# sensor-shield-v5.net
KiCad netlist of a schematic drawn in EasyEDA
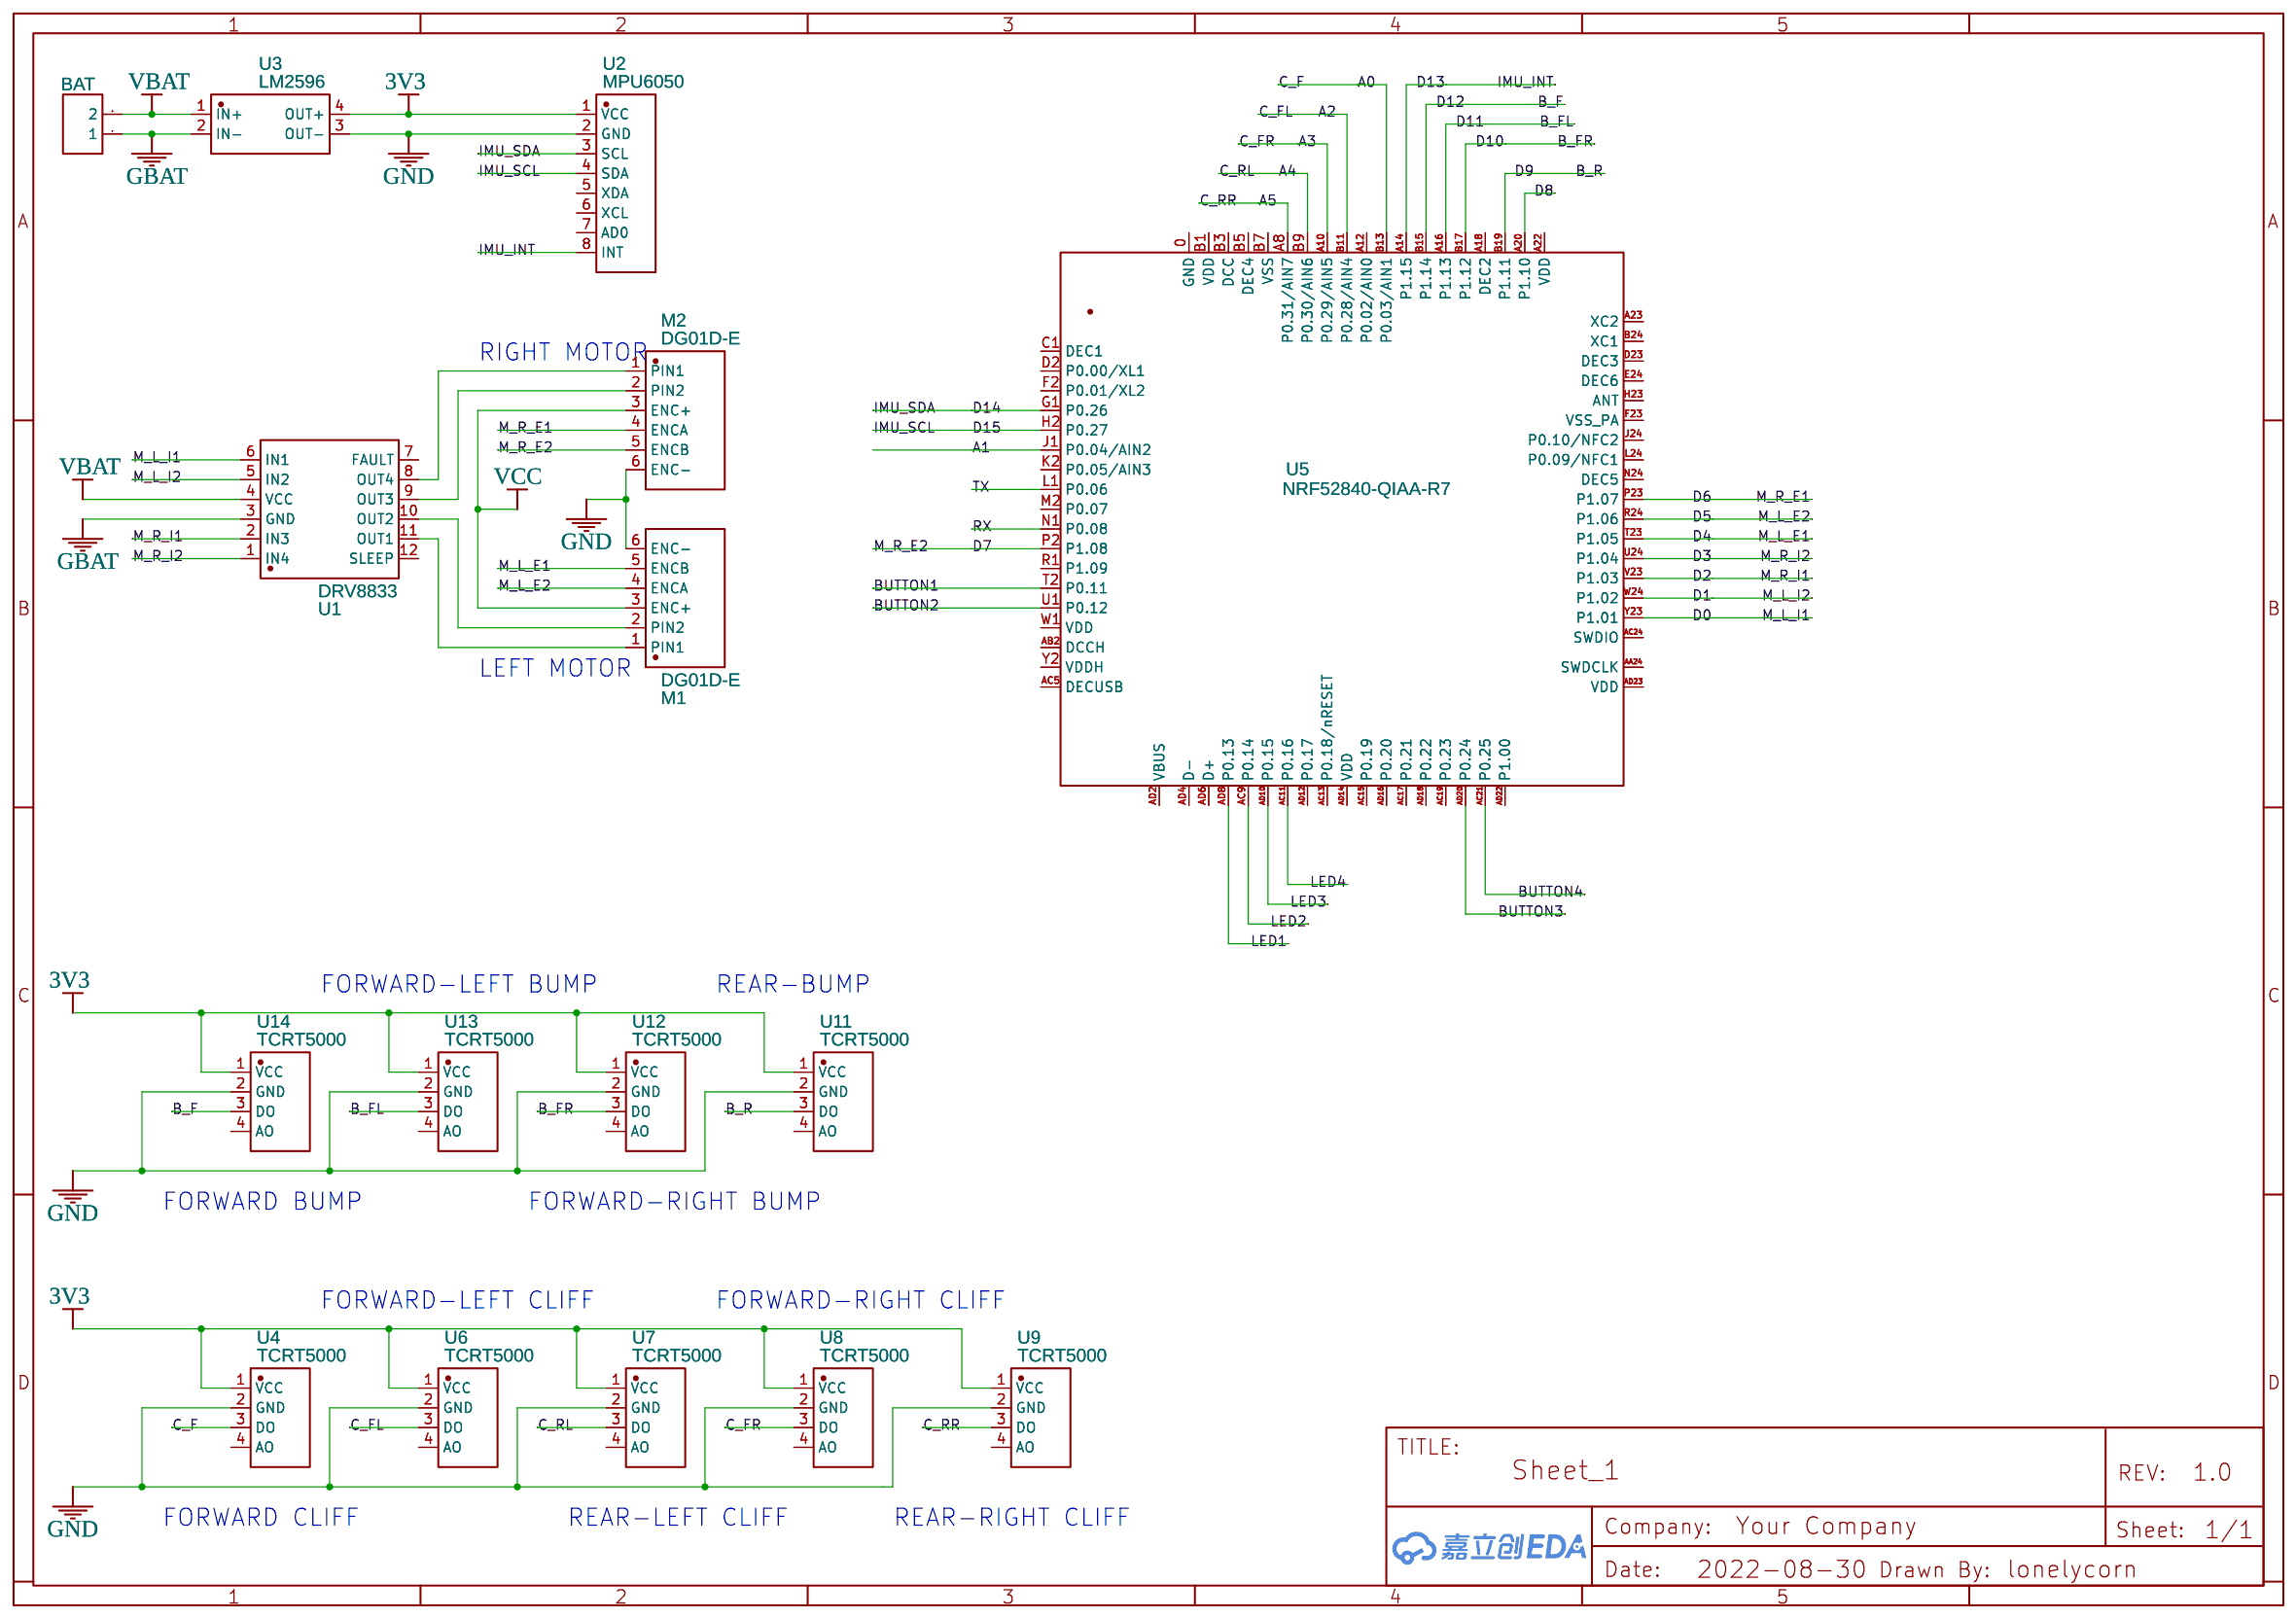
[diagram p0: Sensors]
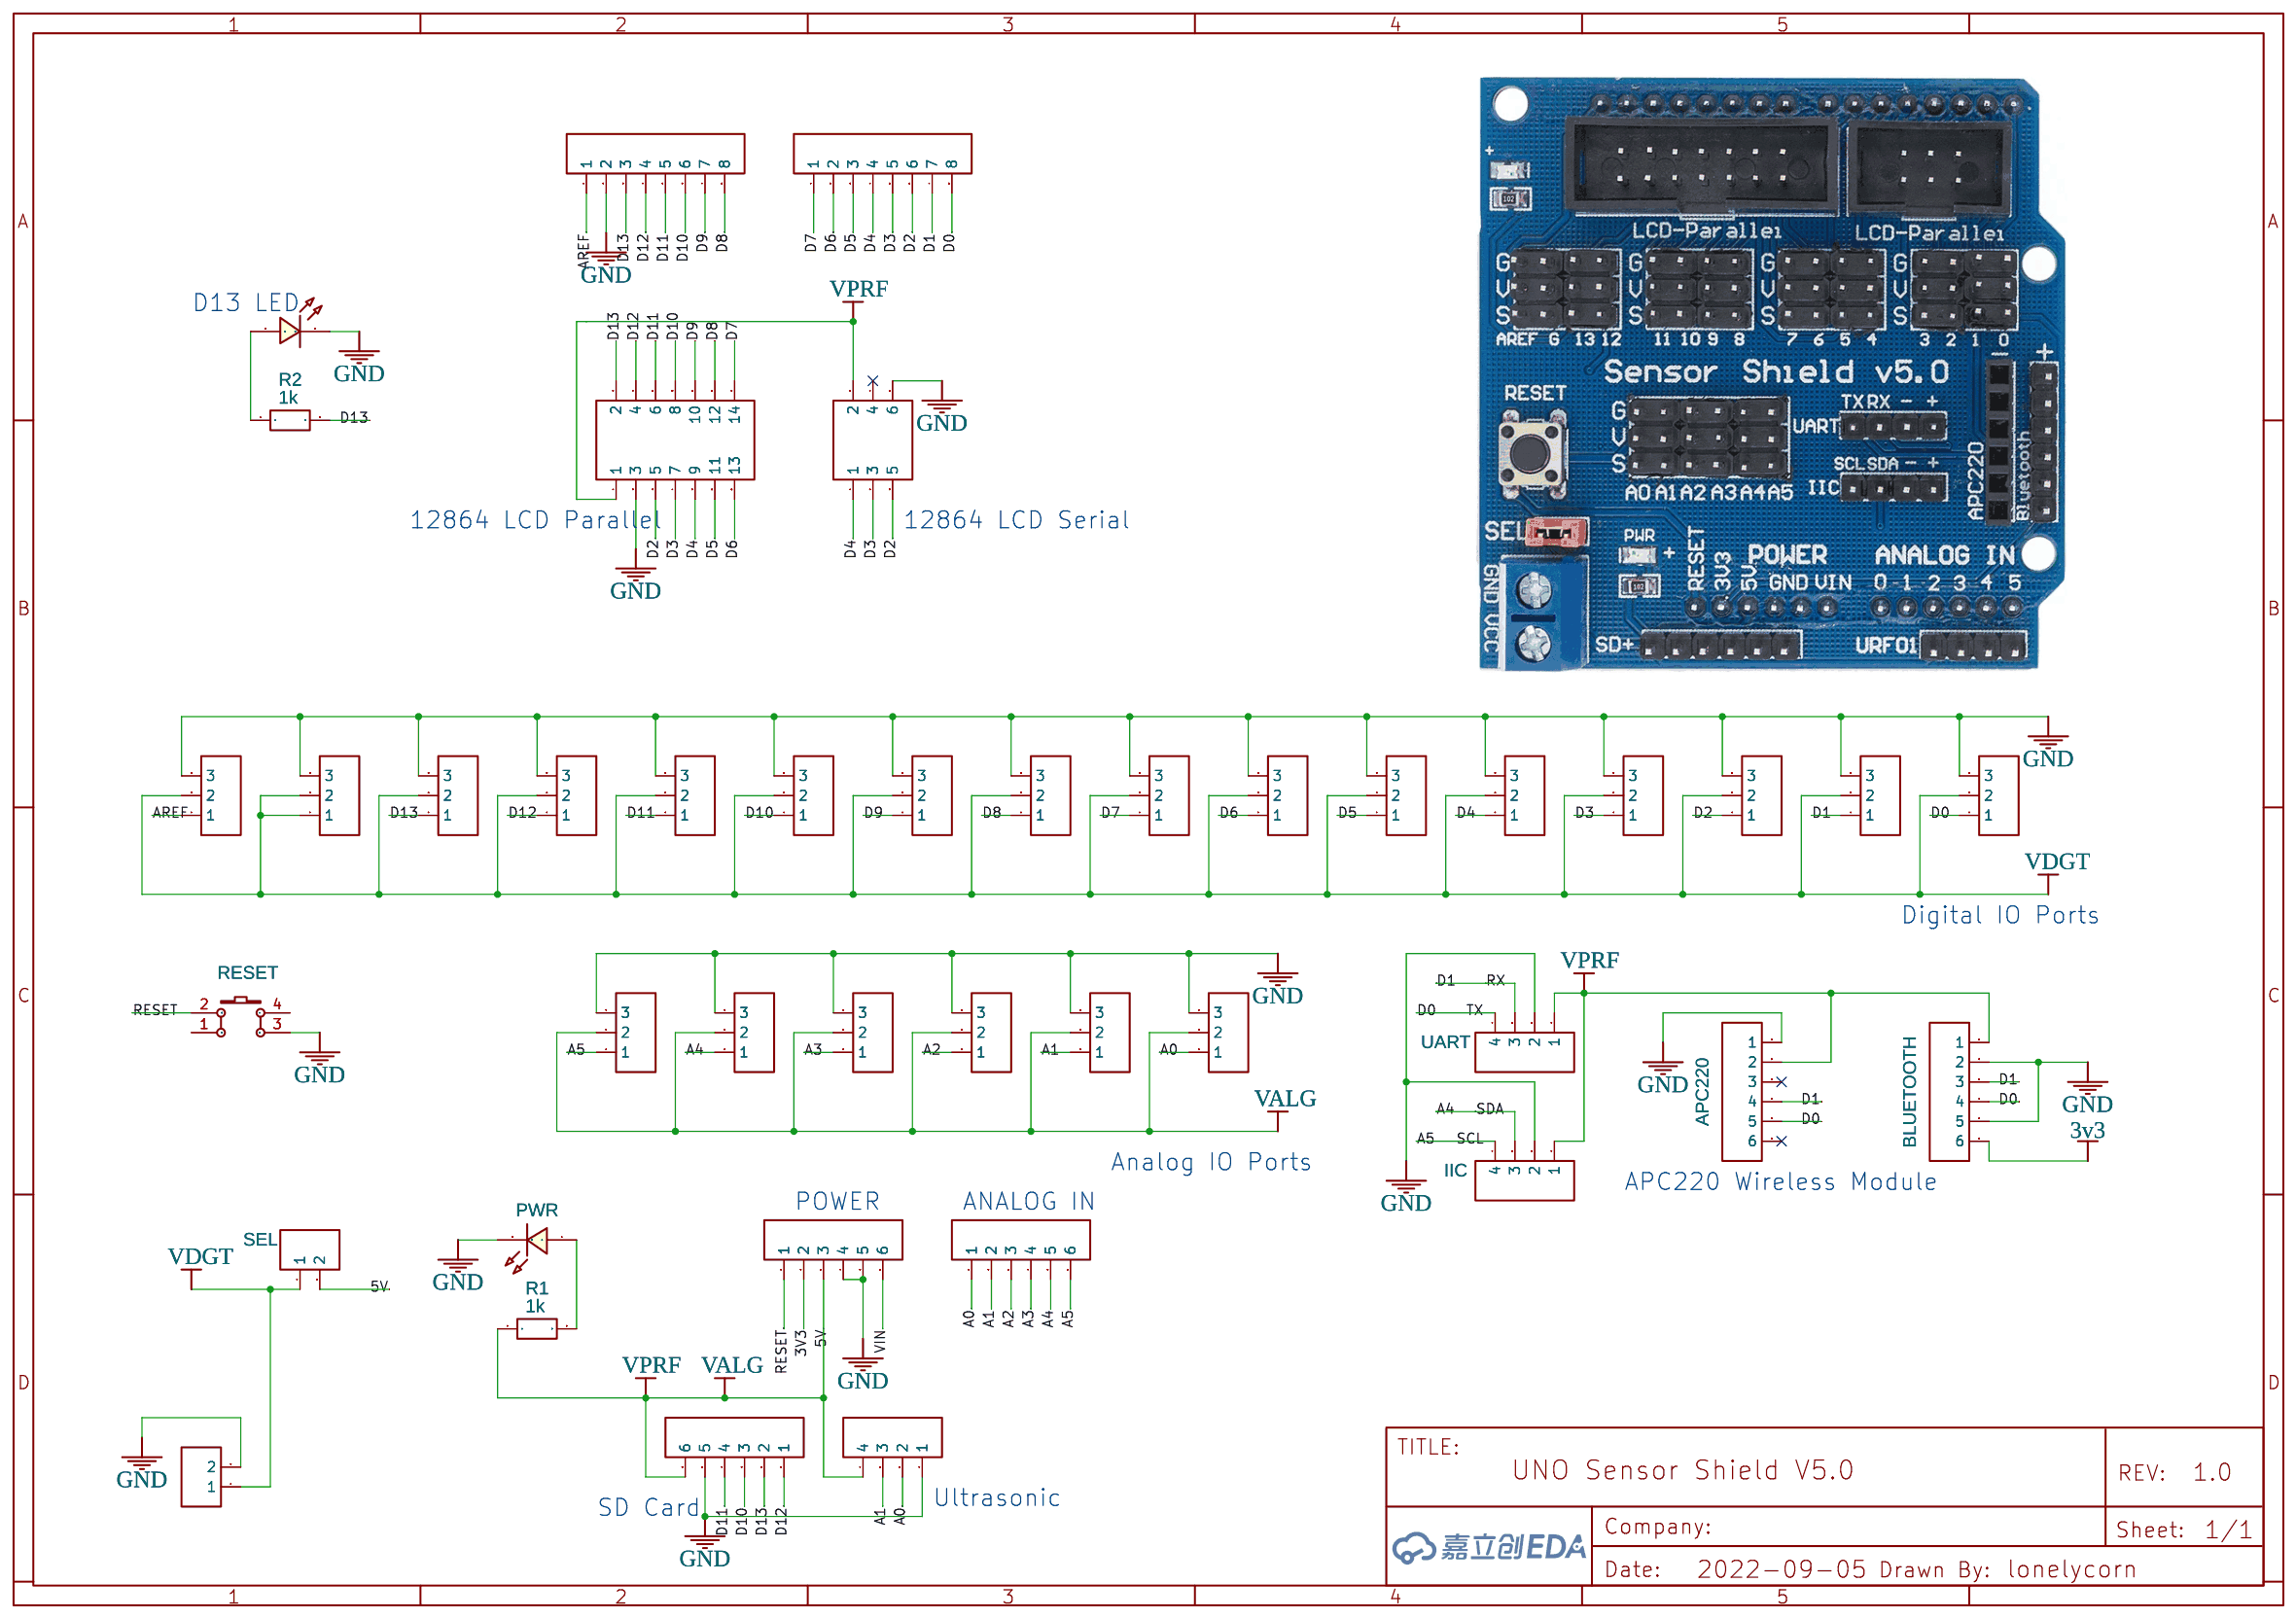
[diagram p1: Sensor Shield v5.0]

(export (version "E")
  (design (tool "Eeschema 10.0.6"))
  (components
    (comp (ref "BAT")
      (value "HDR-F-2.54_1x2")
      (fields (field (name "BOM_Supplier Part") "C49661"))
      (libsource (lib "") (part "HDR-F-2.54_1x2"))
    )
    (comp (ref "M1") (value "DG01D-E") (libsource (lib "") (part "DG01D-E")))
    (comp (ref "M2") (value "DG01D-E") (libsource (lib "") (part "DG01D-E_1")))
    (comp (ref "U1") (value "DRV8833") (libsource (lib "") (part "DRV8833")))
    (comp (ref "U2") (value "MPU6050") (libsource (lib "") (part "MPU6050")))
    (comp (ref "U3") (value "LM2596") (libsource (lib "") (part "LM2596")))
    (comp (ref "U4") (value "TCRT5000") (libsource (lib "") (part "TCRT5000")))
    (comp (ref "U5")
      (value "NRF52840-QIAA-R7")
      (fields (field (name "BOM_Supplier Part") "C1851953"))
      (libsource (lib "") (part "NRF52840-QIAA-R7"))
    )
    (comp (ref "U6") (value "TCRT5000") (libsource (lib "") (part "TCRT5000")))
    (comp (ref "U7") (value "TCRT5000") (libsource (lib "") (part "TCRT5000")))
    (comp (ref "U8") (value "TCRT5000") (libsource (lib "") (part "TCRT5000")))
    (comp (ref "U9") (value "TCRT5000") (libsource (lib "") (part "TCRT5000")))
    (comp (ref "U11") (value "TCRT5000") (libsource (lib "") (part "TCRT5000")))
    (comp (ref "U12") (value "TCRT5000") (libsource (lib "") (part "TCRT5000")))
    (comp (ref "U13") (value "TCRT5000") (libsource (lib "") (part "TCRT5000")))
    (comp (ref "U14") (value "TCRT5000") (libsource (lib "") (part "TCRT5000")))
    (comp (ref "APC220")
      (value "HDR-F-2.54_1x6")
      (fields (field (name "BOM_Supplier Part") "C40877"))
      (libsource (lib "") (part "HDR-F-2.54_1x6_1"))
    )
    (comp (ref "BLUETOOTH")
      (value "HDR-M-2.54_1x6")
      (fields (field (name "BOM_Supplier Part") "C40877"))
      (libsource (lib "") (part "HDR-F-2.54_1x6"))
    )
    (comp (ref "D0")
      (value "HDR-M-2.54_1x3")
      (fields (field (name "BOM_Supplier Part") "C146690"))
      (libsource (lib "") (part "HDR-F-2.54_1x3"))
    )
    (comp (ref "D1")
      (value "HDR-M-2.54_1x3")
      (fields (field (name "BOM_Supplier Part") "C146690"))
      (libsource (lib "") (part "HDR-F-2.54_1x3"))
    )
    (comp (ref "D2")
      (value "HDR-M-2.54_1x3")
      (fields (field (name "BOM_Supplier Part") "C146690"))
      (libsource (lib "") (part "HDR-F-2.54_1x3"))
    )
    (comp (ref "D3")
      (value "HDR-M-2.54_1x3")
      (fields (field (name "BOM_Supplier Part") "C146690"))
      (libsource (lib "") (part "HDR-F-2.54_1x3"))
    )
    (comp (ref "D4")
      (value "HDR-M-2.54_1x3")
      (fields (field (name "BOM_Supplier Part") "C146690"))
      (libsource (lib "") (part "HDR-F-2.54_1x3"))
    )
    (comp (ref "D5")
      (value "HDR-M-2.54_1x3")
      (fields (field (name "BOM_Supplier Part") "C146690"))
      (libsource (lib "") (part "HDR-F-2.54_1x3"))
    )
    (comp (ref "D6")
      (value "HDR-M-2.54_1x3")
      (fields (field (name "BOM_Supplier Part") "C146690"))
      (libsource (lib "") (part "HDR-F-2.54_1x3"))
    )
    (comp (ref "D7")
      (value "HDR-M-2.54_1x3")
      (fields (field (name "BOM_Supplier Part") "C146690"))
      (libsource (lib "") (part "HDR-F-2.54_1x3"))
    )
    (comp (ref "D8")
      (value "HDR-M-2.54_1x3")
      (fields (field (name "BOM_Supplier Part") "C146690"))
      (libsource (lib "") (part "HDR-F-2.54_1x3"))
    )
    (comp (ref "D9")
      (value "HDR-M-2.54_1x3")
      (fields (field (name "BOM_Supplier Part") "C146690"))
      (libsource (lib "") (part "HDR-F-2.54_1x3"))
    )
    (comp (ref "D10")
      (value "HDR-M-2.54_1x3")
      (fields (field (name "BOM_Supplier Part") "C146690"))
      (libsource (lib "") (part "HDR-F-2.54_1x3"))
    )
    (comp (ref "D11")
      (value "HDR-M-2.54_1x3")
      (fields (field (name "BOM_Supplier Part") "C146690"))
      (libsource (lib "") (part "HDR-F-2.54_1x3"))
    )
    (comp (ref "D12")
      (value "HDR-M-2.54_1x3")
      (fields (field (name "BOM_Supplier Part") "C146690"))
      (libsource (lib "") (part "HDR-F-2.54_1x3"))
    )
    (comp (ref "D13")
      (value "HDR-M-2.54_1x3")
      (fields (field (name "BOM_Supplier Part") "C146690"))
      (libsource (lib "") (part "HDR-F-2.54_1x3"))
    )
    (comp (ref "D14")
      (value "HDR-M-2.54_1x3")
      (fields (field (name "BOM_Supplier Part") "C146690"))
      (libsource (lib "") (part "HDR-F-2.54_1x3"))
    )
    (comp (ref "D15")
      (value "HDR-M-2.54_1x3")
      (fields (field (name "BOM_Supplier Part") "C146690"))
      (libsource (lib "") (part "HDR-F-2.54_1x3"))
    )
    (comp (ref "D16")
      (value "HDR-M-2.54_1x3")
      (fields (field (name "BOM_Supplier Part") "C146690"))
      (libsource (lib "") (part "HDR-F-2.54_1x3"))
    )
    (comp (ref "D17")
      (value "HDR-M-2.54_1x3")
      (fields (field (name "BOM_Supplier Part") "C146690"))
      (libsource (lib "") (part "HDR-F-2.54_1x3"))
    )
    (comp (ref "D18")
      (value "HDR-M-2.54_1x3")
      (fields (field (name "BOM_Supplier Part") "C146690"))
      (libsource (lib "") (part "HDR-F-2.54_1x3"))
    )
    (comp (ref "D19")
      (value "HDR-M-2.54_1x3")
      (fields (field (name "BOM_Supplier Part") "C146690"))
      (libsource (lib "") (part "HDR-F-2.54_1x3"))
    )
    (comp (ref "H1")
      (value "HDR-M-2.54_1x3")
      (fields (field (name "BOM_Supplier Part") "C146690"))
      (libsource (lib "") (part "HDR-F-2.54_1x3_1"))
    )
    (comp (ref "H2")
      (value "HDR-M-2.54_1x3")
      (fields (field (name "BOM_Supplier Part") "C146690"))
      (libsource (lib "") (part "HDR-F-2.54_1x3_1"))
    )
    (comp (ref "H4")
      (value "HDR-F-2.54_2x3")
      (fields (field (name "BOM_Supplier Part") "C65114"))
      (libsource (lib "") (part "HDR-F-2.54_2x3"))
    )
    (comp (ref "IIC")
      (value "HDR-M-2.54_1x4")
      (fields (field (name "BOM_Supplier Part") "C225501"))
      (libsource (lib "") (part "HDR-F-2.54_1x4_1"))
    )
    (comp (ref "J1")
      (value "HDR-M-2.54_1x8")
      (fields (field (name "BOM_Supplier Part") "C190820"))
      (libsource (lib "") (part "HDR-M-2.54_1x8"))
    )
    (comp (ref "J2")
      (value "HDR-M-2.54_1x8")
      (fields (field (name "BOM_Supplier Part") "C190820"))
      (libsource (lib "") (part "HDR-M-2.54_1x8"))
    )
    (comp (ref "J3")
      (value "HDR-M-2.54_1x6")
      (fields (field (name "BOM_Supplier Part") "C190819"))
      (libsource (lib "") (part "HDR-M-2.54_1x6"))
    )
    (comp (ref "J4")
      (value "HDR-M-2.54_1x6")
      (fields (field (name "BOM_Supplier Part") "C190819"))
      (libsource (lib "") (part "HDR-M-2.54_1x6"))
    )
    (comp (ref "J5")
      (value "HDR-M-2.54_1x6")
      (fields (field (name "BOM_Supplier Part") "C190819"))
      (libsource (lib "") (part "HDR-M-2.54_1x6_1"))
    )
    (comp (ref "J6")
      (value "HDR-M-2.54_1x4")
      (fields (field (name "BOM_Supplier Part") "C124378"))
      (libsource (lib "") (part "HDR-M-2.54_1x4"))
    )
    (comp (ref "LCD")
      (value "HDR-F-2.54_2x7")
      (fields (field (name "BOM_Supplier Part") "C38844"))
      (libsource (lib "") (part "HDR-F-2.54_2x7"))
    )
    (comp (ref "LED1")
      (value "LED-0603_R")
      (fields
        (field (name "BOM_Manufacturer Part") "19-217/R6C-AL1M2VY/3T")
        (field (name "BOM_Supplier Part") "C72044")
      )
      (libsource (lib "") (part "LED-0603_R_1"))
    )
    (comp (ref "P1") (value "CONN-TH_2P-P5.00") (libsource (lib "") (part "CONN-TH_2P-P5.00")))
    (comp (ref "PWR")
      (value "LED-0603_R")
      (fields
        (field (name "BOM_Manufacturer Part") "19-217/R6C-AL1M2VY/3T")
        (field (name "BOM_Supplier Part") "C72044")
      )
      (libsource (lib "") (part "LED-0603_R"))
    )
    (comp (ref "R1") (value "1k") (libsource (lib "") (part "R_0402_EU")))
    (comp (ref "R2") (value "1k") (libsource (lib "") (part "R_0402_EU")))
    (comp (ref "RESET")
      (value "K4-6×6_SMD")
      (fields
        (field (name "BOM_Manufacturer Part") "K2-6639SP-D4SC-04")
        (field (name "BOM_Supplier Part") "C191626")
      )
      (libsource (lib "") (part "K4-6×6_SMD"))
    )
    (comp (ref "SEL")
      (value "HDR-M-2.54_1x2")
      (fields (field (name "BOM_Supplier Part") "C124375"))
      (libsource (lib "") (part "HDR-M-2.54_1x2"))
    )
    (comp (ref "UART")
      (value "HDR-M-2.54_1x4")
      (fields (field (name "BOM_Supplier Part") "C225501"))
      (libsource (lib "") (part "HDR-F-2.54_1x4"))
    )
  )
  (nets
    (net (code "1") (name "3V3") (class "Default")
      (node (ref "J3") (pin "2") (pinfunction "2_2") (pintype "input"))
      (node (ref "U11") (pin "1") (pinfunction "VCC_1") (pintype "unspecified"))
      (node (ref "U12") (pin "1") (pinfunction "VCC_1") (pintype "unspecified"))
      (node (ref "U13") (pin "1") (pinfunction "VCC_1") (pintype "unspecified"))
      (node (ref "U14") (pin "1") (pinfunction "VCC_1") (pintype "unspecified"))
      (node (ref "U2") (pin "1") (pinfunction "VCC_1") (pintype "unspecified"))
      (node (ref "U3") (pin "4") (pinfunction "OUT+_4") (pintype "unspecified"))
      (node (ref "U4") (pin "1") (pinfunction "VCC_1") (pintype "unspecified"))
      (node (ref "U6") (pin "1") (pinfunction "VCC_1") (pintype "unspecified"))
      (node (ref "U7") (pin "1") (pinfunction "VCC_1") (pintype "unspecified"))
      (node (ref "U8") (pin "1") (pinfunction "VCC_1") (pintype "unspecified"))
      (node (ref "U9") (pin "1") (pinfunction "VCC_1") (pintype "unspecified"))
    )
    (net (code "2") (name "3v3") (class "Default")
      (node (ref "BLUETOOTH") (pin "6") (pinfunction "6_6") (pintype "input"))
    )
    (net (code "3") (name "5V") (class "Default")
      (node (ref "APC220") (pin "2") (pinfunction "2_2") (pintype "input"))
      (node (ref "BLUETOOTH") (pin "1") (pinfunction "1_1") (pintype "input"))
      (node (ref "D14") (pin "2") (pinfunction "2_2") (pintype "input"))
      (node (ref "D15") (pin "2") (pinfunction "2_2") (pintype "input"))
      (node (ref "D16") (pin "2") (pinfunction "2_2") (pintype "input"))
      (node (ref "D17") (pin "2") (pinfunction "2_2") (pintype "input"))
      (node (ref "D18") (pin "2") (pinfunction "2_2") (pintype "input"))
      (node (ref "D19") (pin "2") (pinfunction "2_2") (pintype "input"))
      (node (ref "H4") (pin "2") (pinfunction "2_2") (pintype "input"))
      (node (ref "IIC") (pin "1") (pinfunction "1_1") (pintype "unspecified"))
      (node (ref "J3") (pin "3") (pinfunction "3_3") (pintype "input"))
      (node (ref "J5") (pin "6") (pinfunction "6_6") (pintype "input"))
      (node (ref "J6") (pin "4") (pinfunction "4_4") (pintype "unspecified"))
      (node (ref "LCD") (pin "1") (pinfunction "1_1") (pintype "input"))
      (node (ref "R1") (pin "1") (pinfunction "1_1") (pintype "unspecified"))
      (node (ref "SEL") (pin "2") (pinfunction "2_2") (pintype "unspecified"))
      (node (ref "UART") (pin "1") (pinfunction "1_1") (pintype "unspecified"))
    )
    (net (code "4") (name "A0") (class "Default")
      (node (ref "D19") (pin "1") (pinfunction "1_1") (pintype "input"))
      (node (ref "J4") (pin "1") (pinfunction "1_1") (pintype "input"))
      (node (ref "J6") (pin "2") (pinfunction "2_2") (pintype "unspecified"))
      (node (ref "U4") (pin "3") (pinfunction "DO_3") (pintype "unspecified"))
      (node (ref "U5") (pin "B13") (pinfunction "P0.03/AIN1_B13") (pintype "unspecified"))
    )
    (net (code "5") (name "A1") (class "Default")
      (node (ref "D18") (pin "1") (pinfunction "1_1") (pintype "input"))
      (node (ref "J4") (pin "2") (pinfunction "2_2") (pintype "input"))
      (node (ref "J6") (pin "3") (pinfunction "3_3") (pintype "unspecified"))
      (node (ref "U5") (pin "J1") (pinfunction "P0.04/AIN2_J1") (pintype "unspecified"))
    )
    (net (code "6") (name "A2") (class "Default")
      (node (ref "D17") (pin "1") (pinfunction "1_1") (pintype "input"))
      (node (ref "J4") (pin "3") (pinfunction "3_3") (pintype "input"))
      (node (ref "U5") (pin "B11") (pinfunction "P0.28/AIN4_B11") (pintype "unspecified"))
      (node (ref "U6") (pin "3") (pinfunction "DO_3") (pintype "unspecified"))
    )
    (net (code "7") (name "A3") (class "Default")
      (node (ref "D16") (pin "1") (pinfunction "1_1") (pintype "input"))
      (node (ref "J4") (pin "4") (pinfunction "4_4") (pintype "input"))
      (node (ref "U5") (pin "A10") (pinfunction "P0.29/AIN5_A10") (pintype "unspecified"))
      (node (ref "U8") (pin "3") (pinfunction "DO_3") (pintype "unspecified"))
    )
    (net (code "8") (name "A4") (class "Default")
      (node (ref "D15") (pin "1") (pinfunction "1_1") (pintype "input"))
      (node (ref "IIC") (pin "3") (pinfunction "3_3") (pintype "unspecified"))
      (node (ref "J4") (pin "5") (pinfunction "5_5") (pintype "input"))
      (node (ref "U5") (pin "B9") (pinfunction "P0.30/AIN6_B9") (pintype "unspecified"))
      (node (ref "U7") (pin "3") (pinfunction "DO_3") (pintype "unspecified"))
    )
    (net (code "9") (name "A5") (class "Default")
      (node (ref "D14") (pin "1") (pinfunction "1_1") (pintype "input"))
      (node (ref "IIC") (pin "4") (pinfunction "4_4") (pintype "unspecified"))
      (node (ref "J4") (pin "6") (pinfunction "6_6") (pintype "input"))
      (node (ref "U5") (pin "A8") (pinfunction "P0.31/AIN7_A8") (pintype "unspecified"))
      (node (ref "U9") (pin "3") (pinfunction "DO_3") (pintype "unspecified"))
    )
    (net (code "10") (name "AREF") (class "Default")
      (node (ref "H2") (pin "1") (pinfunction "1_1") (pintype "input"))
      (node (ref "J1") (pin "1") (pinfunction "1_1") (pintype "unspecified"))
    )
    (net (code "11") (name "BUTTON1") (class "Default")
      (node (ref "U5") (pin "T2") (pinfunction "P0.11_T2") (pintype "unspecified"))
    )
    (net (code "12") (name "BUTTON2") (class "Default")
      (node (ref "U5") (pin "U1") (pinfunction "P0.12_U1") (pintype "unspecified"))
    )
    (net (code "13") (name "BUTTON3") (class "Default")
      (node (ref "U5") (pin "AD20") (pinfunction "P0.24_AD20") (pintype "unspecified"))
    )
    (net (code "14") (name "BUTTON4") (class "Default")
      (node (ref "U5") (pin "AC21") (pinfunction "P0.25_AC21") (pintype "unspecified"))
    )
    (net (code "15") (name "B_F") (class "Default")
      (node (ref "D12") (pin "1") (pinfunction "1_1") (pintype "input"))
      (node (ref "J1") (pin "4") (pinfunction "4_4") (pintype "unspecified"))
      (node (ref "J5") (pin "1") (pinfunction "1_1") (pintype "input"))
      (node (ref "LCD") (pin "4") (pinfunction "4_4") (pintype "input"))
      (node (ref "U14") (pin "3") (pinfunction "DO_3") (pintype "unspecified"))
      (node (ref "U5") (pin "B15") (pinfunction "P1.14_B15") (pintype "unspecified"))
    )
    (net (code "16") (name "B_FL") (class "Default")
      (node (ref "D11") (pin "1") (pinfunction "1_1") (pintype "input"))
      (node (ref "J1") (pin "5") (pinfunction "5_5") (pintype "unspecified"))
      (node (ref "J5") (pin "4") (pinfunction "4_4") (pintype "input"))
      (node (ref "LCD") (pin "6") (pinfunction "6_6") (pintype "input"))
      (node (ref "U13") (pin "3") (pinfunction "DO_3") (pintype "unspecified"))
      (node (ref "U5") (pin "A16") (pinfunction "P1.13_A16") (pintype "unspecified"))
    )
    (net (code "17") (name "B_FR") (class "Default")
      (node (ref "D10") (pin "1") (pinfunction "1_1") (pintype "input"))
      (node (ref "J1") (pin "6") (pinfunction "6_6") (pintype "unspecified"))
      (node (ref "J5") (pin "3") (pinfunction "3_3") (pintype "input"))
      (node (ref "LCD") (pin "8") (pinfunction "8_8") (pintype "input"))
      (node (ref "U12") (pin "3") (pinfunction "DO_3") (pintype "unspecified"))
      (node (ref "U5") (pin "B17") (pinfunction "P1.12_B17") (pintype "unspecified"))
    )
    (net (code "18") (name "B_R") (class "Default")
      (node (ref "D9") (pin "1") (pinfunction "1_1") (pintype "input"))
      (node (ref "J1") (pin "7") (pinfunction "7_7") (pintype "unspecified"))
      (node (ref "LCD") (pin "10") (pinfunction "10_10") (pintype "input"))
      (node (ref "U11") (pin "3") (pinfunction "DO_3") (pintype "unspecified"))
      (node (ref "U5") (pin "B19") (pinfunction "P1.11_B19") (pintype "unspecified"))
    )
    (net (code "19") (name "D0") (class "Default")
      (node (ref "APC220") (pin "5") (pinfunction "5_5") (pintype "input"))
      (node (ref "BLUETOOTH") (pin "4") (pinfunction "4_4") (pintype "input"))
      (node (ref "D0") (pin "1") (pinfunction "1_1") (pintype "input"))
      (node (ref "J2") (pin "8") (pinfunction "8_8") (pintype "unspecified"))
      (node (ref "U1") (pin "6") (pinfunction "IN1_6") (pintype "unspecified"))
      (node (ref "U5") (pin "L1") (pinfunction "P0.06_L1") (pintype "unspecified"))
      (node (ref "U5") (pin "Y23") (pinfunction "P1.01_Y23") (pintype "unspecified"))
      (node (ref "UART") (pin "4") (pinfunction "4_4") (pintype "unspecified"))
    )
    (net (code "20") (name "D1") (class "Default")
      (node (ref "APC220") (pin "4") (pinfunction "4_4") (pintype "input"))
      (node (ref "BLUETOOTH") (pin "3") (pinfunction "3_3") (pintype "input"))
      (node (ref "D1") (pin "1") (pinfunction "1_1") (pintype "input"))
      (node (ref "J2") (pin "7") (pinfunction "7_7") (pintype "unspecified"))
      (node (ref "U1") (pin "5") (pinfunction "IN2_5") (pintype "unspecified"))
      (node (ref "U5") (pin "N1") (pinfunction "P0.08_N1") (pintype "unspecified"))
      (node (ref "U5") (pin "W24") (pinfunction "P1.02_W24") (pintype "unspecified"))
      (node (ref "UART") (pin "3") (pinfunction "3_3") (pintype "unspecified"))
    )
    (net (code "21") (name "D2") (class "Default")
      (node (ref "D2") (pin "1") (pinfunction "1_1") (pintype "input"))
      (node (ref "H4") (pin "5") (pinfunction "5_5") (pintype "input"))
      (node (ref "J2") (pin "6") (pinfunction "6_6") (pintype "unspecified"))
      (node (ref "LCD") (pin "5") (pinfunction "5_5") (pintype "input"))
      (node (ref "U1") (pin "2") (pinfunction "IN3_2") (pintype "unspecified"))
      (node (ref "U5") (pin "V23") (pinfunction "P1.03_V23") (pintype "unspecified"))
    )
    (net (code "22") (name "D3") (class "Default")
      (node (ref "D3") (pin "1") (pinfunction "1_1") (pintype "input"))
      (node (ref "H4") (pin "3") (pinfunction "3_3") (pintype "input"))
      (node (ref "J2") (pin "5") (pinfunction "5_5") (pintype "unspecified"))
      (node (ref "LCD") (pin "7") (pinfunction "7_7") (pintype "input"))
      (node (ref "U1") (pin "1") (pinfunction "IN4_1") (pintype "unspecified"))
      (node (ref "U5") (pin "U24") (pinfunction "P1.04_U24") (pintype "unspecified"))
    )
    (net (code "23") (name "D4") (class "Default")
      (node (ref "D4") (pin "1") (pinfunction "1_1") (pintype "input"))
      (node (ref "H4") (pin "1") (pinfunction "1_1") (pintype "input"))
      (node (ref "J2") (pin "4") (pinfunction "4_4") (pintype "unspecified"))
      (node (ref "LCD") (pin "9") (pinfunction "9_9") (pintype "input"))
      (node (ref "M1") (pin "5") (pinfunction "ENCB_5") (pintype "unspecified"))
      (node (ref "U5") (pin "T23") (pinfunction "P1.05_T23") (pintype "unspecified"))
    )
    (net (code "24") (name "D5") (class "Default")
      (node (ref "D5") (pin "1") (pinfunction "1_1") (pintype "input"))
      (node (ref "J2") (pin "3") (pinfunction "3_3") (pintype "unspecified"))
      (node (ref "LCD") (pin "11") (pinfunction "11_11") (pintype "input"))
      (node (ref "M1") (pin "4") (pinfunction "ENCA_4") (pintype "unspecified"))
      (node (ref "U5") (pin "R24") (pinfunction "P1.06_R24") (pintype "unspecified"))
    )
    (net (code "25") (name "D6") (class "Default")
      (node (ref "D6") (pin "1") (pinfunction "1_1") (pintype "input"))
      (node (ref "J2") (pin "2") (pinfunction "2_2") (pintype "unspecified"))
      (node (ref "LCD") (pin "13") (pinfunction "13_13") (pintype "input"))
      (node (ref "M2") (pin "4") (pinfunction "ENCA_4") (pintype "unspecified"))
      (node (ref "U5") (pin "P23") (pinfunction "P1.07_P23") (pintype "unspecified"))
    )
    (net (code "26") (name "D7") (class "Default")
      (node (ref "D7") (pin "1") (pinfunction "1_1") (pintype "input"))
      (node (ref "J2") (pin "1") (pinfunction "1_1") (pintype "unspecified"))
      (node (ref "LCD") (pin "14") (pinfunction "14_14") (pintype "input"))
      (node (ref "M2") (pin "5") (pinfunction "ENCB_5") (pintype "unspecified"))
      (node (ref "U5") (pin "P2") (pinfunction "P1.08_P2") (pintype "unspecified"))
    )
    (net (code "27") (name "D8") (class "Default")
      (node (ref "D8") (pin "1") (pinfunction "1_1") (pintype "input"))
      (node (ref "J1") (pin "8") (pinfunction "8_8") (pintype "unspecified"))
      (node (ref "LCD") (pin "12") (pinfunction "12_12") (pintype "input"))
      (node (ref "U5") (pin "A20") (pinfunction "P1.10_A20") (pintype "unspecified"))
    )
    (net (code "28") (name "D13") (class "Default")
      (node (ref "D13") (pin "1") (pinfunction "1_1") (pintype "input"))
      (node (ref "J1") (pin "3") (pinfunction "3_3") (pintype "unspecified"))
      (node (ref "J5") (pin "2") (pinfunction "2_2") (pintype "input"))
      (node (ref "LCD") (pin "2") (pinfunction "2_2") (pintype "input"))
      (node (ref "R2") (pin "2") (pinfunction "2_2") (pintype "unspecified"))
      (node (ref "U2") (pin "8") (pinfunction "INT_8") (pintype "unspecified"))
      (node (ref "U5") (pin "A14") (pinfunction "P1.15_A14") (pintype "unspecified"))
    )
    (net (code "29") (name "D14") (class "Default")
      (node (ref "U2") (pin "3") (pinfunction "SCL_3") (pintype "unspecified"))
      (node (ref "U5") (pin "G1") (pinfunction "P0.26_G1") (pintype "unspecified"))
    )
    (net (code "30") (name "D15") (class "Default")
      (node (ref "U2") (pin "4") (pinfunction "SDA_4") (pintype "unspecified"))
      (node (ref "U5") (pin "H2") (pinfunction "P0.27_H2") (pintype "unspecified"))
    )
    (net (code "31") (name "GBAT") (class "Default")
      (node (ref "BAT") (pin "1") (pinfunction "1_1") (pintype "input"))
      (node (ref "U1") (pin "3") (pinfunction "GND_3") (pintype "unspecified"))
      (node (ref "U3") (pin "2") (pinfunction "IN-_2") (pintype "unspecified"))
    )
    (net (code "32") (name "GND") (class "Default")
      (node (ref "APC220") (pin "1") (pinfunction "1_1") (pintype "input"))
      (node (ref "BLUETOOTH") (pin "2") (pinfunction "2_2") (pintype "input"))
      (node (ref "BLUETOOTH") (pin "5") (pinfunction "5_5") (pintype "input"))
      (node (ref "D0") (pin "3") (pinfunction "3_3") (pintype "input"))
      (node (ref "D1") (pin "3") (pinfunction "3_3") (pintype "input"))
      (node (ref "D10") (pin "3") (pinfunction "3_3") (pintype "input"))
      (node (ref "D11") (pin "3") (pinfunction "3_3") (pintype "input"))
      (node (ref "D12") (pin "3") (pinfunction "3_3") (pintype "input"))
      (node (ref "D13") (pin "3") (pinfunction "3_3") (pintype "input"))
      (node (ref "D14") (pin "3") (pinfunction "3_3") (pintype "input"))
      (node (ref "D15") (pin "3") (pinfunction "3_3") (pintype "input"))
      (node (ref "D16") (pin "3") (pinfunction "3_3") (pintype "input"))
      (node (ref "D17") (pin "3") (pinfunction "3_3") (pintype "input"))
      (node (ref "D18") (pin "3") (pinfunction "3_3") (pintype "input"))
      (node (ref "D19") (pin "3") (pinfunction "3_3") (pintype "input"))
      (node (ref "D2") (pin "3") (pinfunction "3_3") (pintype "input"))
      (node (ref "D3") (pin "3") (pinfunction "3_3") (pintype "input"))
      (node (ref "D4") (pin "3") (pinfunction "3_3") (pintype "input"))
      (node (ref "D5") (pin "3") (pinfunction "3_3") (pintype "input"))
      (node (ref "D6") (pin "3") (pinfunction "3_3") (pintype "input"))
      (node (ref "D7") (pin "3") (pinfunction "3_3") (pintype "input"))
      (node (ref "D8") (pin "3") (pinfunction "3_3") (pintype "input"))
      (node (ref "D9") (pin "3") (pinfunction "3_3") (pintype "input"))
      (node (ref "H1") (pin "3") (pinfunction "3_3") (pintype "input"))
      (node (ref "H2") (pin "3") (pinfunction "3_3") (pintype "input"))
      (node (ref "H4") (pin "6") (pinfunction "6_6") (pintype "input"))
      (node (ref "IIC") (pin "2") (pinfunction "2_2") (pintype "unspecified"))
      (node (ref "J1") (pin "2") (pinfunction "2_2") (pintype "unspecified"))
      (node (ref "J3") (pin "4") (pinfunction "4_4") (pintype "input"))
      (node (ref "J3") (pin "5") (pinfunction "5_5") (pintype "input"))
      (node (ref "J5") (pin "5") (pinfunction "5_5") (pintype "input"))
      (node (ref "J6") (pin "1") (pinfunction "1_1") (pintype "unspecified"))
      (node (ref "LCD") (pin "3") (pinfunction "3_3") (pintype "input"))
      (node (ref "LED1") (pin "2") (pinfunction "2_2") (pintype "unspecified"))
      (node (ref "M1") (pin "6") (pinfunction "ENC-_6") (pintype "unspecified"))
      (node (ref "M2") (pin "6") (pinfunction "ENC-_6") (pintype "unspecified"))
      (node (ref "P1") (pin "2") (pinfunction "2_2") (pintype "unspecified"))
      (node (ref "PWR") (pin "2") (pinfunction "2_2") (pintype "unspecified"))
      (node (ref "RESET") (pin "3") (pinfunction "3_3") (pintype "unspecified"))
      (node (ref "U11") (pin "2") (pinfunction "GND_2") (pintype "unspecified"))
      (node (ref "U12") (pin "2") (pinfunction "GND_2") (pintype "unspecified"))
      (node (ref "U13") (pin "2") (pinfunction "GND_2") (pintype "unspecified"))
      (node (ref "U14") (pin "2") (pinfunction "GND_2") (pintype "unspecified"))
      (node (ref "U2") (pin "2") (pinfunction "GND_2") (pintype "unspecified"))
      (node (ref "U3") (pin "3") (pinfunction "OUT-_3") (pintype "unspecified"))
      (node (ref "U4") (pin "2") (pinfunction "GND_2") (pintype "unspecified"))
      (node (ref "U6") (pin "2") (pinfunction "GND_2") (pintype "unspecified"))
      (node (ref "U7") (pin "2") (pinfunction "GND_2") (pintype "unspecified"))
      (node (ref "U8") (pin "2") (pinfunction "GND_2") (pintype "unspecified"))
      (node (ref "U9") (pin "2") (pinfunction "GND_2") (pintype "unspecified"))
      (node (ref "UART") (pin "2") (pinfunction "2_2") (pintype "unspecified"))
    )
    (net (code "33") (name "LED1") (class "Default")
      (node (ref "U5") (pin "AD8") (pinfunction "P0.13_AD8") (pintype "unspecified"))
    )
    (net (code "34") (name "LED2") (class "Default")
      (node (ref "U5") (pin "AC9") (pinfunction "P0.14_AC9") (pintype "unspecified"))
    )
    (net (code "35") (name "LED3") (class "Default")
      (node (ref "U5") (pin "AD10") (pinfunction "P0.15_AD10") (pintype "unspecified"))
    )
    (net (code "36") (name "LED4") (class "Default")
      (node (ref "U5") (pin "AC11") (pinfunction "P0.16_AC11") (pintype "unspecified"))
    )
    (net (code "37") (name "Net-(LED1-Pad1)") (class "Default")
      (node (ref "LED1") (pin "1") (pinfunction "1_1") (pintype "unspecified"))
      (node (ref "R2") (pin "1") (pinfunction "1_1") (pintype "unspecified"))
    )
    (net (code "38") (name "Net-(M1-PIN1)") (class "Default")
      (node (ref "M1") (pin "1") (pinfunction "PIN1_1") (pintype "unspecified"))
      (node (ref "U1") (pin "11") (pinfunction "OUT1_11") (pintype "unspecified"))
    )
    (net (code "39") (name "Net-(M1-PIN2)") (class "Default")
      (node (ref "M1") (pin "2") (pinfunction "PIN2_2") (pintype "unspecified"))
      (node (ref "U1") (pin "10") (pinfunction "OUT2_10") (pintype "unspecified"))
    )
    (net (code "40") (name "Net-(M2-PIN1)") (class "Default")
      (node (ref "M2") (pin "1") (pinfunction "PIN1_1") (pintype "unspecified"))
      (node (ref "U1") (pin "8") (pinfunction "OUT4_8") (pintype "unspecified"))
    )
    (net (code "41") (name "Net-(M2-PIN2)") (class "Default")
      (node (ref "M2") (pin "2") (pinfunction "PIN2_2") (pintype "unspecified"))
      (node (ref "U1") (pin "9") (pinfunction "OUT3_9") (pintype "unspecified"))
    )
    (net (code "42") (name "Net-(PWR-Pad1)") (class "Default")
      (node (ref "PWR") (pin "1") (pinfunction "1_1") (pintype "unspecified"))
      (node (ref "R1") (pin "2") (pinfunction "2_2") (pintype "unspecified"))
    )
    (net (code "43") (name "RESET") (class "Default")
      (node (ref "J3") (pin "1") (pinfunction "1_1") (pintype "input"))
      (node (ref "RESET") (pin "2") (pinfunction "2_2") (pintype "unspecified"))
    )
    (net (code "44") (name "VBAT") (class "Default")
      (node (ref "BAT") (pin "2") (pinfunction "2_2") (pintype "input"))
      (node (ref "U1") (pin "4") (pinfunction "VCC_4") (pintype "unspecified"))
      (node (ref "U3") (pin "1") (pinfunction "IN+_1") (pintype "unspecified"))
    )
    (net (code "45") (name "VCC") (class "Default")
      (node (ref "M1") (pin "3") (pinfunction "ENC+_3") (pintype "unspecified"))
      (node (ref "M2") (pin "3") (pinfunction "ENC+_3") (pintype "unspecified"))
    )
    (net (code "46") (name "VDGT") (class "Default")
      (node (ref "D0") (pin "2") (pinfunction "2_2") (pintype "input"))
      (node (ref "D1") (pin "2") (pinfunction "2_2") (pintype "input"))
      (node (ref "D10") (pin "2") (pinfunction "2_2") (pintype "input"))
      (node (ref "D11") (pin "2") (pinfunction "2_2") (pintype "input"))
      (node (ref "D12") (pin "2") (pinfunction "2_2") (pintype "input"))
      (node (ref "D13") (pin "2") (pinfunction "2_2") (pintype "input"))
      (node (ref "D2") (pin "2") (pinfunction "2_2") (pintype "input"))
      (node (ref "D3") (pin "2") (pinfunction "2_2") (pintype "input"))
      (node (ref "D4") (pin "2") (pinfunction "2_2") (pintype "input"))
      (node (ref "D5") (pin "2") (pinfunction "2_2") (pintype "input"))
      (node (ref "D6") (pin "2") (pinfunction "2_2") (pintype "input"))
      (node (ref "D7") (pin "2") (pinfunction "2_2") (pintype "input"))
      (node (ref "D8") (pin "2") (pinfunction "2_2") (pintype "input"))
      (node (ref "D9") (pin "2") (pinfunction "2_2") (pintype "input"))
      (node (ref "H1") (pin "1") (pinfunction "1_1") (pintype "input"))
      (node (ref "H1") (pin "2") (pinfunction "2_2") (pintype "input"))
      (node (ref "H2") (pin "2") (pinfunction "2_2") (pintype "input"))
      (node (ref "P1") (pin "1") (pinfunction "1_1") (pintype "unspecified"))
      (node (ref "SEL") (pin "1") (pinfunction "1_1") (pintype "unspecified"))
    )
    (net (code "47") (name "VIN") (class "Default")
      (node (ref "J3") (pin "6") (pinfunction "6_6") (pintype "input"))
    )
    (net (code "48") (name "unconnected-(APC220-Pad3)") (class "Default")
      (node (ref "APC220") (pin "3") (pinfunction "3_3") (pintype "input+no_connect"))
    )
    (net (code "49") (name "unconnected-(APC220-Pad6)") (class "Default")
      (node (ref "APC220") (pin "6") (pinfunction "6_6") (pintype "input+no_connect"))
    )
    (net (code "50") (name "unconnected-(H4-Pad4)") (class "Default")
      (node (ref "H4") (pin "4") (pinfunction "4_4") (pintype "input+no_connect"))
    )
    (net (code "51") (name "unconnected-(RESET-Pad1)") (class "Default")
      (node (ref "RESET") (pin "1") (pinfunction "1_1") (pintype "unspecified"))
    )
    (net (code "52") (name "unconnected-(RESET-Pad4)") (class "Default")
      (node (ref "RESET") (pin "4") (pinfunction "4_4") (pintype "unspecified"))
    )
    (net (code "53") (name "unconnected-(U1-FAULT-Pad7)") (class "Default")
      (node (ref "U1") (pin "7") (pinfunction "FAULT_7") (pintype "unspecified"))
    )
    (net (code "54") (name "unconnected-(U1-SLEEP-Pad12)") (class "Default")
      (node (ref "U1") (pin "12") (pinfunction "SLEEP_12") (pintype "unspecified"))
    )
    (net (code "55") (name "unconnected-(U2-AD0-Pad7)") (class "Default")
      (node (ref "U2") (pin "7") (pinfunction "AD0_7") (pintype "unspecified"))
    )
    (net (code "56") (name "unconnected-(U2-XCL-Pad6)") (class "Default")
      (node (ref "U2") (pin "6") (pinfunction "XCL_6") (pintype "unspecified"))
    )
    (net (code "57") (name "unconnected-(U2-XDA-Pad5)") (class "Default")
      (node (ref "U2") (pin "5") (pinfunction "XDA_5") (pintype "unspecified"))
    )
    (net (code "58") (name "unconnected-(U4-AO-Pad4)") (class "Default")
      (node (ref "U4") (pin "4") (pinfunction "AO_4") (pintype "unspecified"))
    )
    (net (code "59") (name "unconnected-(U5-ANT-PadH23)") (class "Default")
      (node (ref "U5") (pin "H23") (pinfunction "ANT_H23") (pintype "unspecified"))
    )
    (net (code "60") (name "unconnected-(U5-D+-PadAD6)") (class "Default")
      (node (ref "U5") (pin "AD6") (pinfunction "D+_AD6") (pintype "unspecified"))
    )
    (net (code "61") (name "unconnected-(U5-D--PadAD4)") (class "Default")
      (node (ref "U5") (pin "AD4") (pinfunction "D-_AD4") (pintype "unspecified"))
    )
    (net (code "62") (name "unconnected-(U5-DCC-PadB3)") (class "Default")
      (node (ref "U5") (pin "B3") (pinfunction "DCC_B3") (pintype "unspecified"))
    )
    (net (code "63") (name "unconnected-(U5-DCCH-PadAB2)") (class "Default")
      (node (ref "U5") (pin "AB2") (pinfunction "DCCH_AB2") (pintype "unspecified"))
    )
    (net (code "64") (name "unconnected-(U5-DEC1-PadC1)") (class "Default")
      (node (ref "U5") (pin "C1") (pinfunction "DEC1_C1") (pintype "unspecified"))
    )
    (net (code "65") (name "unconnected-(U5-DEC2-PadA18)") (class "Default")
      (node (ref "U5") (pin "A18") (pinfunction "DEC2_A18") (pintype "unspecified"))
    )
    (net (code "66") (name "unconnected-(U5-DEC3-PadD23)") (class "Default")
      (node (ref "U5") (pin "D23") (pinfunction "DEC3_D23") (pintype "unspecified"))
    )
    (net (code "67") (name "unconnected-(U5-DEC4-PadB5)") (class "Default")
      (node (ref "U5") (pin "B5") (pinfunction "DEC4_B5") (pintype "unspecified"))
    )
    (net (code "68") (name "unconnected-(U5-DEC5-PadN24)") (class "Default")
      (node (ref "U5") (pin "N24") (pinfunction "DEC5_N24") (pintype "unspecified"))
    )
    (net (code "69") (name "unconnected-(U5-DEC6-PadE24)") (class "Default")
      (node (ref "U5") (pin "E24") (pinfunction "DEC6_E24") (pintype "unspecified"))
    )
    (net (code "70") (name "unconnected-(U5-DECUSB-PadAC5)") (class "Default")
      (node (ref "U5") (pin "AC5") (pinfunction "DECUSB_AC5") (pintype "unspecified"))
    )
    (net (code "71") (name "unconnected-(U5-GND-Pad0)") (class "Default")
      (node (ref "U5") (pin "0") (pinfunction "GND_0") (pintype "unspecified"))
    )
    (net (code "72") (name "unconnected-(U5-P0.00{slash}XL1-PadD2)") (class "Default")
      (node (ref "U5") (pin "D2") (pinfunction "P0.00/XL1_D2") (pintype "unspecified"))
    )
    (net (code "73") (name "unconnected-(U5-P0.01{slash}XL2-PadF2)") (class "Default")
      (node (ref "U5") (pin "F2") (pinfunction "P0.01/XL2_F2") (pintype "unspecified"))
    )
    (net (code "74") (name "unconnected-(U5-P0.02{slash}AIN0-PadA12)") (class "Default")
      (node (ref "U5") (pin "A12") (pinfunction "P0.02/AIN0_A12") (pintype "unspecified"))
    )
    (net (code "75") (name "unconnected-(U5-P0.05{slash}AIN3-PadK2)") (class "Default")
      (node (ref "U5") (pin "K2") (pinfunction "P0.05/AIN3_K2") (pintype "unspecified"))
    )
    (net (code "76") (name "unconnected-(U5-P0.07-PadM2)") (class "Default")
      (node (ref "U5") (pin "M2") (pinfunction "P0.07_M2") (pintype "unspecified"))
    )
    (net (code "77") (name "unconnected-(U5-P0.09{slash}NFC1-PadL24)") (class "Default")
      (node (ref "U5") (pin "L24") (pinfunction "P0.09/NFC1_L24") (pintype "unspecified"))
    )
    (net (code "78") (name "unconnected-(U5-P0.10{slash}NFC2-PadJ24)") (class "Default")
      (node (ref "U5") (pin "J24") (pinfunction "P0.10/NFC2_J24") (pintype "unspecified"))
    )
    (net (code "79") (name "unconnected-(U5-P0.17-PadAD12)") (class "Default")
      (node (ref "U5") (pin "AD12") (pinfunction "P0.17_AD12") (pintype "unspecified"))
    )
    (net (code "80") (name "unconnected-(U5-P0.18{slash}nRESET-PadAC13)") (class "Default")
      (node (ref "U5") (pin "AC13") (pinfunction "P0.18/nRESET_AC13") (pintype "unspecified"))
    )
    (net (code "81") (name "unconnected-(U5-P0.19-PadAC15)") (class "Default")
      (node (ref "U5") (pin "AC15") (pinfunction "P0.19_AC15") (pintype "unspecified"))
    )
    (net (code "82") (name "unconnected-(U5-P0.20-PadAD16)") (class "Default")
      (node (ref "U5") (pin "AD16") (pinfunction "P0.20_AD16") (pintype "unspecified"))
    )
    (net (code "83") (name "unconnected-(U5-P0.21-PadAC17)") (class "Default")
      (node (ref "U5") (pin "AC17") (pinfunction "P0.21_AC17") (pintype "unspecified"))
    )
    (net (code "84") (name "unconnected-(U5-P0.22-PadAD18)") (class "Default")
      (node (ref "U5") (pin "AD18") (pinfunction "P0.22_AD18") (pintype "unspecified"))
    )
    (net (code "85") (name "unconnected-(U5-P0.23-PadAC19)") (class "Default")
      (node (ref "U5") (pin "AC19") (pinfunction "P0.23_AC19") (pintype "unspecified"))
    )
    (net (code "86") (name "unconnected-(U5-P1.00-PadAD22)") (class "Default")
      (node (ref "U5") (pin "AD22") (pinfunction "P1.00_AD22") (pintype "unspecified"))
    )
    (net (code "87") (name "unconnected-(U5-P1.09-PadR1)") (class "Default")
      (node (ref "U5") (pin "R1") (pinfunction "P1.09_R1") (pintype "unspecified"))
    )
    (net (code "88") (name "unconnected-(U5-SWDCLK-PadAA24)") (class "Default")
      (node (ref "U5") (pin "AA24") (pinfunction "SWDCLK_AA24") (pintype "unspecified"))
    )
    (net (code "89") (name "unconnected-(U5-SWDIO-PadAC24)") (class "Default")
      (node (ref "U5") (pin "AC24") (pinfunction "SWDIO_AC24") (pintype "unspecified"))
    )
    (net (code "90") (name "unconnected-(U5-VBUS-PadAD2)") (class "Default")
      (node (ref "U5") (pin "AD2") (pinfunction "VBUS_AD2") (pintype "unspecified"))
    )
    (net (code "91") (name "unconnected-(U5-VDD-PadA22)") (class "Default")
      (node (ref "U5") (pin "A22") (pinfunction "VDD_A22") (pintype "unspecified"))
    )
    (net (code "92") (name "unconnected-(U5-VDD-PadAD14)") (class "Default")
      (node (ref "U5") (pin "AD14") (pinfunction "VDD_AD14") (pintype "unspecified"))
    )
    (net (code "93") (name "unconnected-(U5-VDD-PadAD23)") (class "Default")
      (node (ref "U5") (pin "AD23") (pinfunction "VDD_AD23") (pintype "unspecified"))
    )
    (net (code "94") (name "unconnected-(U5-VDD-PadB1)") (class "Default")
      (node (ref "U5") (pin "B1") (pinfunction "VDD_B1") (pintype "unspecified"))
    )
    (net (code "95") (name "unconnected-(U5-VDD-PadW1)") (class "Default")
      (node (ref "U5") (pin "W1") (pinfunction "VDD_W1") (pintype "unspecified"))
    )
    (net (code "96") (name "unconnected-(U5-VDDH-PadY2)") (class "Default")
      (node (ref "U5") (pin "Y2") (pinfunction "VDDH_Y2") (pintype "unspecified"))
    )
    (net (code "97") (name "unconnected-(U5-VSS-PadB7)") (class "Default")
      (node (ref "U5") (pin "B7") (pinfunction "VSS_B7") (pintype "unspecified"))
    )
    (net (code "98") (name "unconnected-(U5-VSS_PA-PadF23)") (class "Default")
      (node (ref "U5") (pin "F23") (pinfunction "VSS_PA_F23") (pintype "unspecified"))
    )
    (net (code "99") (name "unconnected-(U5-XC1-PadB24)") (class "Default")
      (node (ref "U5") (pin "B24") (pinfunction "XC1_B24") (pintype "unspecified"))
    )
    (net (code "100") (name "unconnected-(U5-XC2-PadA23)") (class "Default")
      (node (ref "U5") (pin "A23") (pinfunction "XC2_A23") (pintype "unspecified"))
    )
    (net (code "101") (name "unconnected-(U6-AO-Pad4)") (class "Default")
      (node (ref "U6") (pin "4") (pinfunction "AO_4") (pintype "unspecified"))
    )
    (net (code "102") (name "unconnected-(U7-AO-Pad4)") (class "Default")
      (node (ref "U7") (pin "4") (pinfunction "AO_4") (pintype "unspecified"))
    )
    (net (code "103") (name "unconnected-(U8-AO-Pad4)") (class "Default")
      (node (ref "U8") (pin "4") (pinfunction "AO_4") (pintype "unspecified"))
    )
    (net (code "104") (name "unconnected-(U9-AO-Pad4)") (class "Default")
      (node (ref "U9") (pin "4") (pinfunction "AO_4") (pintype "unspecified"))
    )
    (net (code "105") (name "unconnected-(U11-AO-Pad4)") (class "Default")
      (node (ref "U11") (pin "4") (pinfunction "AO_4") (pintype "unspecified"))
    )
    (net (code "106") (name "unconnected-(U12-AO-Pad4)") (class "Default")
      (node (ref "U12") (pin "4") (pinfunction "AO_4") (pintype "unspecified"))
    )
    (net (code "107") (name "unconnected-(U13-AO-Pad4)") (class "Default")
      (node (ref "U13") (pin "4") (pinfunction "AO_4") (pintype "unspecified"))
    )
    (net (code "108") (name "unconnected-(U14-AO-Pad4)") (class "Default")
      (node (ref "U14") (pin "4") (pinfunction "AO_4") (pintype "unspecified"))
    )
  )
)
